# ATmega.net
KiCad netlist of a schematic drawn in Altium Designer
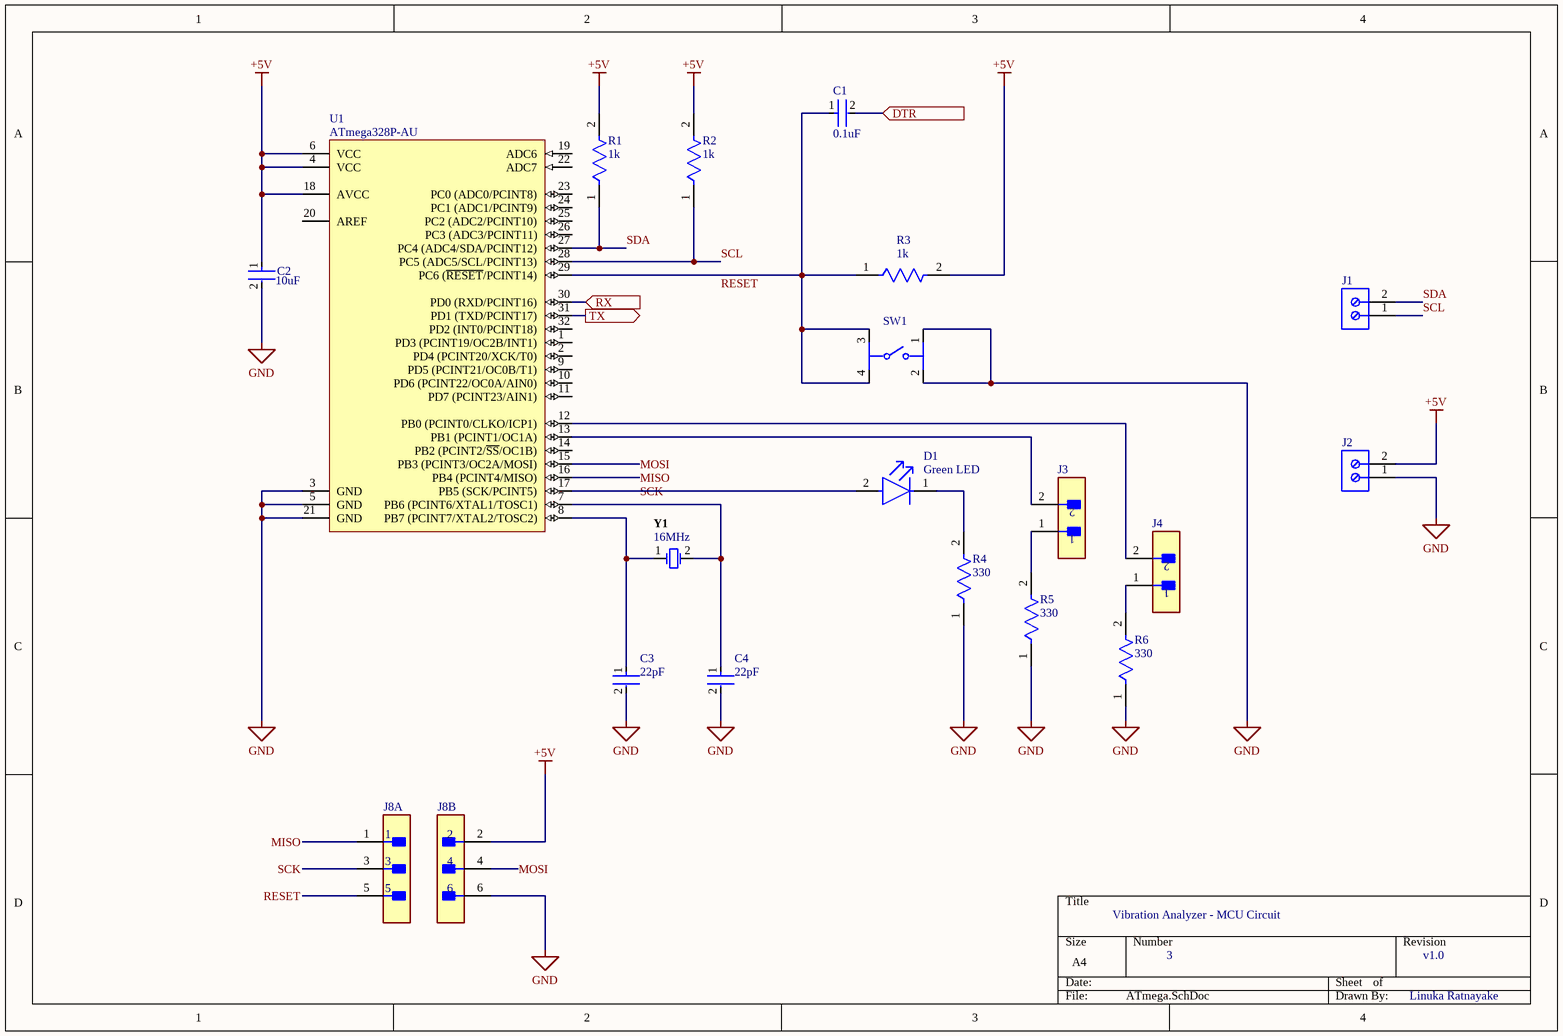
[diagram p0: ATmega.SchDoc]

(export (version "E")
  (design (tool "Eeschema 10.0.6"))
  (components
    (comp (ref "C1")
      (value "GRM31M1X1H104JA01L")
      (footprint "FP-GRM31M-0_15-IPC_A")
      (fields
        (field (name "VOLTAGE") "50V")
        (field (name "TOLERANCE") "5%")
        (field (name "CAPACITANCE") "0.1uF")
      )
      (libsource (lib "Altium Content Vault") (part "b4654b650e69147ec39a6b967a45e02"))
    )
    (comp (ref "C2")
      (value "GRM31M1X1H104JA01L")
      (footprint "FP-GRM31M-0_15-IPC_A")
      (fields
        (field (name "VOLTAGE") "50V")
        (field (name "TOLERANCE") "5%")
        (field (name "CAPACITANCE") "10uF")
      )
      (libsource (lib "Altium Content Vault") (part "b4654b650e69147ec39a6b967a45e02"))
    )
    (comp (ref "C3")
      (value "GRM31M1X1H104JA01L")
      (footprint "FP-GRM31M-0_15-IPC_A")
      (fields
        (field (name "VOLTAGE") "50V")
        (field (name "TOLERANCE") "5%")
        (field (name "CAPACITANCE") "22pF")
      )
      (libsource (lib "Altium Content Vault") (part "b4654b650e69147ec39a6b967a45e02"))
    )
    (comp (ref "C4")
      (value "GRM31M1X1H104JA01L")
      (footprint "FP-GRM31M-0_15-IPC_A")
      (fields
        (field (name "VOLTAGE") "50V")
        (field (name "TOLERANCE") "5%")
        (field (name "CAPACITANCE") "22pF")
      )
      (libsource (lib "Altium Content Vault") (part "b4654b650e69147ec39a6b967a45e02"))
    )
    (comp (ref "D1")
      (value "HSMG-C150")
      (footprint "FP-HSMG-C150-MFG")
      (description "LED GREEN DIFFUSED 1206 SMD")
      (fields
        (field (name "MANUFACTURER") "Broadcom")
        (field (name "OCTOPART") "https://octopart.com/hsmg-c150-broadcom-71131304")
        (field (name "COLOR") "Green LED")
      )
      (libsource (lib "Altium Content Vault") (part "8706943c75ba83719d021d2fdc84c58"))
    )
    (comp (ref "J1")
      (value "691214110002")
      (footprint "691214110002")
      (fields (field (name "VOLTAGE") "300V"))
      (libsource (lib "Altium Content Vault") (part "TBL - 1R - 02P - Screw"))
    )
    (comp (ref "J2")
      (value "691214110002")
      (footprint "691214110002")
      (fields (field (name "VOLTAGE") "300V"))
      (libsource (lib "Altium Content Vault") (part "TBL - 1R - 02P - Screw"))
    )
    (comp (ref "J3")
      (value "B2B-XH-A(LF)(SN)")
      (footprint "FP-B2B-XH-A_LF_SN-MFG")
      (description "CONN HEADER VERT 2POS 2.5MM")
      (libsource (lib "Altium Content Vault") (part "3bc925449376181038e59eaffc5286c"))
    )
    (comp (ref "J4")
      (value "B2B-XH-A(LF)(SN)")
      (footprint "FP-B2B-XH-A_LF_SN-MFG")
      (description "CONN HEADER VERT 2POS 2.5MM")
      (libsource (lib "Altium Content Vault") (part "3bc925449376181038e59eaffc5286c"))
    )
    (comp (ref "J8")
      (value "M20-9980346")
      (footprint "FP-M20-9980346-MFG")
      (description "CONN HEADER VERT 6POS 2.54MM")
      (fields
        (field (name "MANUFACTURER") "Harwin")
        (field (name "OCTOPART") "https://octopart.com/m20-9980346-harwin-5436545")
      )
      (libsource (lib "") (part "2654a11fb13586ecb194516b1c997bc_1"))
    )
    (comp (ref "R1")
      (value "MCR18EZPF30R0")
      (footprint "FP-MCR18-IPC_B")
      (description "Thick Film Chip Resistor, 1206, 30Ω, 1%, 100ppm/°C, 0.25W, 200V")
      (fields (field (name "RESISTANCE") "1k") (field (name "TOLERANCE") "1%"))
      (libsource (lib "Altium Content Vault") (part "1029c3af85768c4190bb7ad29bc67b5"))
    )
    (comp (ref "R2")
      (value "MCR18EZPF30R0")
      (footprint "FP-MCR18-IPC_B")
      (description "Thick Film Chip Resistor, 1206, 30Ω, 1%, 100ppm/°C, 0.25W, 200V")
      (fields (field (name "RESISTANCE") "1k") (field (name "TOLERANCE") "1%"))
      (libsource (lib "Altium Content Vault") (part "1029c3af85768c4190bb7ad29bc67b5"))
    )
    (comp (ref "R3")
      (value "MCR18EZPF30R0")
      (footprint "FP-MCR18-IPC_B")
      (description "Thick Film Chip Resistor, 1206, 30Ω, 1%, 100ppm/°C, 0.25W, 200V")
      (fields (field (name "RESISTANCE") "1k") (field (name "TOLERANCE") "1%"))
      (libsource (lib "Altium Content Vault") (part "1029c3af85768c4190bb7ad29bc67b5"))
    )
    (comp (ref "R4")
      (value "MCR18EZPF30R0")
      (footprint "FP-MCR18-IPC_B")
      (description "Thick Film Chip Resistor, 1206, 30Ω, 1%, 100ppm/°C, 0.25W, 200V")
      (fields (field (name "RESISTANCE") "330") (field (name "TOLERANCE") "1%"))
      (libsource (lib "Altium Content Vault") (part "1029c3af85768c4190bb7ad29bc67b5"))
    )
    (comp (ref "R5")
      (value "MCR18EZPF30R0")
      (footprint "FP-MCR18-IPC_B")
      (description "Thick Film Chip Resistor, 1206, 30Ω, 1%, 100ppm/°C, 0.25W, 200V")
      (fields (field (name "RESISTANCE") "330") (field (name "TOLERANCE") "1%"))
      (libsource (lib "Altium Content Vault") (part "1029c3af85768c4190bb7ad29bc67b5"))
    )
    (comp (ref "R6")
      (value "MCR18EZPF30R0")
      (footprint "FP-MCR18-IPC_B")
      (description "Thick Film Chip Resistor, 1206, 30Ω, 1%, 100ppm/°C, 0.25W, 200V")
      (fields (field (name "RESISTANCE") "330") (field (name "TOLERANCE") "1%"))
      (libsource (lib "Altium Content Vault") (part "1029c3af85768c4190bb7ad29bc67b5"))
    )
    (comp (ref "SW1")
      (value "PTS645SM43SMTR92LFS")
      (footprint "FP-PTS645SM43SMTR92LFS-MFG")
      (description "SWITCH TACTILE SPST-NO 0.05A 12V")
      (libsource (lib "Altium Content Vault") (part "1adf0dd01260c80cf25a44bfd6b99ba"))
    )
    (comp (ref "U1")
      (value "ATmega328P-AU")
      (footprint "32A_M")
      (libsource (lib "Altium Content Vault") (part "MC-8B-ATM48-SQ32"))
    )
    (comp (ref "Y1")
      (value "FOXSLF/160-20")
      (footprint "FOX-FOXSLF160-20")
      (description "Resistance Weld Thru-Hole Crystal, 16 MHz, -20 to 70 degC, 2-Pin THD, RoHS, Bulk")
      (fields (field (name "TOLERANCE") "1%") (field (name "FREQUENCY") "16MHz"))
      (libsource (lib "Altium Content Vault") (part "XTAL-1-2-2"))
    )
  )
  (nets
    (net (code "1") (name "+5V") (class "Default")
      (node (ref "C2") (pin "1") (pinfunction "1_1") (pintype "passive"))
      (node (ref "J2") (pin "2") (pinfunction "2_2") (pintype "passive"))
      (node (ref "J8") (pin "2") (pinfunction "2_2") (pintype "passive"))
      (node (ref "R1") (pin "2") (pinfunction "2_2") (pintype "passive"))
      (node (ref "R2") (pin "2") (pinfunction "2_2") (pintype "passive"))
      (node (ref "R3") (pin "2") (pinfunction "2_2") (pintype "passive"))
      (node (ref "U1") (pin "18") (pinfunction "AVCC_18") (pintype "power_in"))
      (node (ref "U1") (pin "4") (pinfunction "VCC_4") (pintype "power_in"))
      (node (ref "U1") (pin "6") (pinfunction "VCC_6") (pintype "power_in"))
    )
    (net (code "2") (name "/DTR") (class "Default")
      (node (ref "C1") (pin "2") (pinfunction "2_2") (pintype "passive"))
    )
    (net (code "3") (name "/MISO") (class "Default")
      (node (ref "J8") (pin "1") (pinfunction "1_1") (pintype "passive"))
      (node (ref "U1") (pin "16") (pinfunction "PB4_(PCINT4/MISO)_16") (pintype "bidirectional"))
    )
    (net (code "4") (name "/MOSI") (class "Default")
      (node (ref "J8") (pin "4") (pinfunction "4_4") (pintype "passive"))
      (node (ref "U1") (pin "15") (pinfunction "PB3_(PCINT3/OC2A/MOSI)_15") (pintype "bidirectional"))
    )
    (net (code "5") (name "/RESET") (class "Default")
      (node (ref "C1") (pin "1") (pinfunction "1_1") (pintype "passive"))
      (node (ref "J8") (pin "5") (pinfunction "5_5") (pintype "passive"))
      (node (ref "R3") (pin "1") (pinfunction "1_1") (pintype "passive"))
      (node (ref "SW1") (pin "3") (pinfunction "3_3") (pintype "passive"))
      (node (ref "SW1") (pin "4") (pinfunction "4_4") (pintype "passive"))
      (node (ref "U1") (pin "29") (pinfunction "PC6_(~{RESET}/PCINT14)_29") (pintype "bidirectional"))
    )
    (net (code "6") (name "/RX") (class "Default")
      (node (ref "U1") (pin "30") (pinfunction "PD0_(RXD/PCINT16)_30") (pintype "bidirectional"))
    )
    (net (code "7") (name "/SCK") (class "Default")
      (node (ref "D1") (pin "2") (pinfunction "A_2") (pintype "passive"))
      (node (ref "J8") (pin "3") (pinfunction "3_3") (pintype "passive"))
      (node (ref "U1") (pin "17") (pinfunction "PB5_(SCK/PCINT5)_17") (pintype "bidirectional"))
    )
    (net (code "8") (name "/SCL") (class "Default")
      (node (ref "J1") (pin "1") (pinfunction "1_1") (pintype "passive"))
      (node (ref "R2") (pin "1") (pinfunction "1_1") (pintype "passive"))
      (node (ref "U1") (pin "28") (pinfunction "PC5_(ADC5/SCL/PCINT13)_28") (pintype "bidirectional"))
    )
    (net (code "9") (name "/SDA") (class "Default")
      (node (ref "J1") (pin "2") (pinfunction "2_2") (pintype "passive"))
      (node (ref "R1") (pin "1") (pinfunction "1_1") (pintype "passive"))
      (node (ref "U1") (pin "27") (pinfunction "PC4_(ADC4/SDA/PCINT12)_27") (pintype "bidirectional"))
    )
    (net (code "10") (name "/TX") (class "Default")
      (node (ref "U1") (pin "31") (pinfunction "PD1_(TXD/PCINT17)_31") (pintype "bidirectional"))
    )
    (net (code "11") (name "GND") (class "Default")
      (node (ref "C2") (pin "2") (pinfunction "2_2") (pintype "passive"))
      (node (ref "C3") (pin "2") (pinfunction "2_2") (pintype "passive"))
      (node (ref "C4") (pin "2") (pinfunction "2_2") (pintype "passive"))
      (node (ref "J2") (pin "1") (pinfunction "1_1") (pintype "passive"))
      (node (ref "J8") (pin "6") (pinfunction "6_6") (pintype "passive"))
      (node (ref "R4") (pin "1") (pinfunction "1_1") (pintype "passive"))
      (node (ref "R5") (pin "1") (pinfunction "1_1") (pintype "passive"))
      (node (ref "R6") (pin "1") (pinfunction "1_1") (pintype "passive"))
      (node (ref "SW1") (pin "1") (pinfunction "1_1") (pintype "passive"))
      (node (ref "SW1") (pin "2") (pinfunction "2_2") (pintype "passive"))
      (node (ref "U1") (pin "21") (pinfunction "GND_21") (pintype "power_in"))
      (node (ref "U1") (pin "3") (pinfunction "GND_3") (pintype "power_in"))
      (node (ref "U1") (pin "5") (pinfunction "GND_5") (pintype "power_in"))
    )
    (net (code "12") (name "Net-(D1-C)") (class "Default")
      (node (ref "D1") (pin "1") (pinfunction "C_1") (pintype "passive"))
      (node (ref "R4") (pin "2") (pinfunction "2_2") (pintype "passive"))
    )
    (net (code "13") (name "Net-(J3-Pad1)") (class "Default")
      (node (ref "J3") (pin "1") (pinfunction "1_1") (pintype "passive"))
      (node (ref "R5") (pin "2") (pinfunction "2_2") (pintype "passive"))
    )
    (net (code "14") (name "Net-(J4-Pad1)") (class "Default")
      (node (ref "J4") (pin "1") (pinfunction "1_1") (pintype "passive"))
      (node (ref "R6") (pin "2") (pinfunction "2_2") (pintype "passive"))
    )
    (net (code "15") (name "Net-(U1-PB0_(PCINT0{slash}CLKO{slash}ICP1))") (class "Default")
      (node (ref "J4") (pin "2") (pinfunction "2_2") (pintype "passive"))
      (node (ref "U1") (pin "12") (pinfunction "PB0_(PCINT0/CLKO/ICP1)_12") (pintype "bidirectional"))
    )
    (net (code "16") (name "Net-(U1-PB1_(PCINT1{slash}OC1A))") (class "Default")
      (node (ref "J3") (pin "2") (pinfunction "2_2") (pintype "passive"))
      (node (ref "U1") (pin "13") (pinfunction "PB1_(PCINT1/OC1A)_13") (pintype "bidirectional"))
    )
    (net (code "17") (name "Net-(U1-PB6_(PCINT6{slash}XTAL1{slash}TOSC1))") (class "Default")
      (node (ref "C4") (pin "1") (pinfunction "1_1") (pintype "passive"))
      (node (ref "U1") (pin "7") (pinfunction "PB6_(PCINT6/XTAL1/TOSC1)_7") (pintype "bidirectional"))
      (node (ref "Y1") (pin "2") (pinfunction "2_2") (pintype "passive"))
    )
    (net (code "18") (name "Net-(U1-PB7_(PCINT7{slash}XTAL2{slash}TOSC2))") (class "Default")
      (node (ref "C3") (pin "1") (pinfunction "1_1") (pintype "passive"))
      (node (ref "U1") (pin "8") (pinfunction "PB7_(PCINT7/XTAL2/TOSC2)_8") (pintype "bidirectional"))
      (node (ref "Y1") (pin "1") (pinfunction "1_1") (pintype "passive"))
    )
    (net (code "19") (name "unconnected-(U1-ADC6-Pad19)") (class "Default")
      (node (ref "U1") (pin "19") (pinfunction "ADC6_19") (pintype "input"))
    )
    (net (code "20") (name "unconnected-(U1-ADC7-Pad22)") (class "Default")
      (node (ref "U1") (pin "22") (pinfunction "ADC7_22") (pintype "input"))
    )
    (net (code "21") (name "unconnected-(U1-AREF-Pad20)") (class "Default")
      (node (ref "U1") (pin "20") (pinfunction "AREF_20") (pintype "passive"))
    )
    (net (code "22") (name "unconnected-(U1-PB2_(PCINT2{slash}~{SS}{slash}OC1B)-Pad14)") (class "Default")
      (node (ref "U1") (pin "14") (pinfunction "PB2_(PCINT2/~{SS}/OC1B)_14") (pintype "bidirectional"))
    )
    (net (code "23") (name "unconnected-(U1-PC0_(ADC0{slash}PCINT8)-Pad23)") (class "Default")
      (node (ref "U1") (pin "23") (pinfunction "PC0_(ADC0/PCINT8)_23") (pintype "bidirectional"))
    )
    (net (code "24") (name "unconnected-(U1-PC1_(ADC1{slash}PCINT9)-Pad24)") (class "Default")
      (node (ref "U1") (pin "24") (pinfunction "PC1_(ADC1/PCINT9)_24") (pintype "bidirectional"))
    )
    (net (code "25") (name "unconnected-(U1-PC2_(ADC2{slash}PCINT10)-Pad25)") (class "Default")
      (node (ref "U1") (pin "25") (pinfunction "PC2_(ADC2/PCINT10)_25") (pintype "bidirectional"))
    )
    (net (code "26") (name "unconnected-(U1-PC3_(ADC3{slash}PCINT11)-Pad26)") (class "Default")
      (node (ref "U1") (pin "26") (pinfunction "PC3_(ADC3/PCINT11)_26") (pintype "bidirectional"))
    )
    (net (code "27") (name "unconnected-(U1-PD2_(INT0{slash}PCINT18)-Pad32)") (class "Default")
      (node (ref "U1") (pin "32") (pinfunction "PD2_(INT0/PCINT18)_32") (pintype "bidirectional"))
    )
    (net (code "28") (name "unconnected-(U1-PD3_(PCINT19{slash}OC2B{slash}INT1)-Pad1)") (class "Default")
      (node (ref "U1") (pin "1") (pinfunction "PD3_(PCINT19/OC2B/INT1)_1") (pintype "bidirectional"))
    )
    (net (code "29") (name "unconnected-(U1-PD4_(PCINT20{slash}XCK{slash}T0)-Pad2)") (class "Default")
      (node (ref "U1") (pin "2") (pinfunction "PD4_(PCINT20/XCK/T0)_2") (pintype "bidirectional"))
    )
    (net (code "30") (name "unconnected-(U1-PD5_(PCINT21{slash}OC0B{slash}T1)-Pad9)") (class "Default")
      (node (ref "U1") (pin "9") (pinfunction "PD5_(PCINT21/OC0B/T1)_9") (pintype "bidirectional"))
    )
    (net (code "31") (name "unconnected-(U1-PD6_(PCINT22{slash}OC0A{slash}AIN0)-Pad10)") (class "Default")
      (node (ref "U1") (pin "10") (pinfunction "PD6_(PCINT22/OC0A/AIN0)_10") (pintype "bidirectional"))
    )
    (net (code "32") (name "unconnected-(U1-PD7_(PCINT23{slash}AIN1)-Pad11)") (class "Default")
      (node (ref "U1") (pin "11") (pinfunction "PD7_(PCINT23/AIN1)_11") (pintype "bidirectional"))
    )
  )
)
